# HEADERS_HAS_CCU.net
KiCad netlist of a schematic drawn in Altium Designer
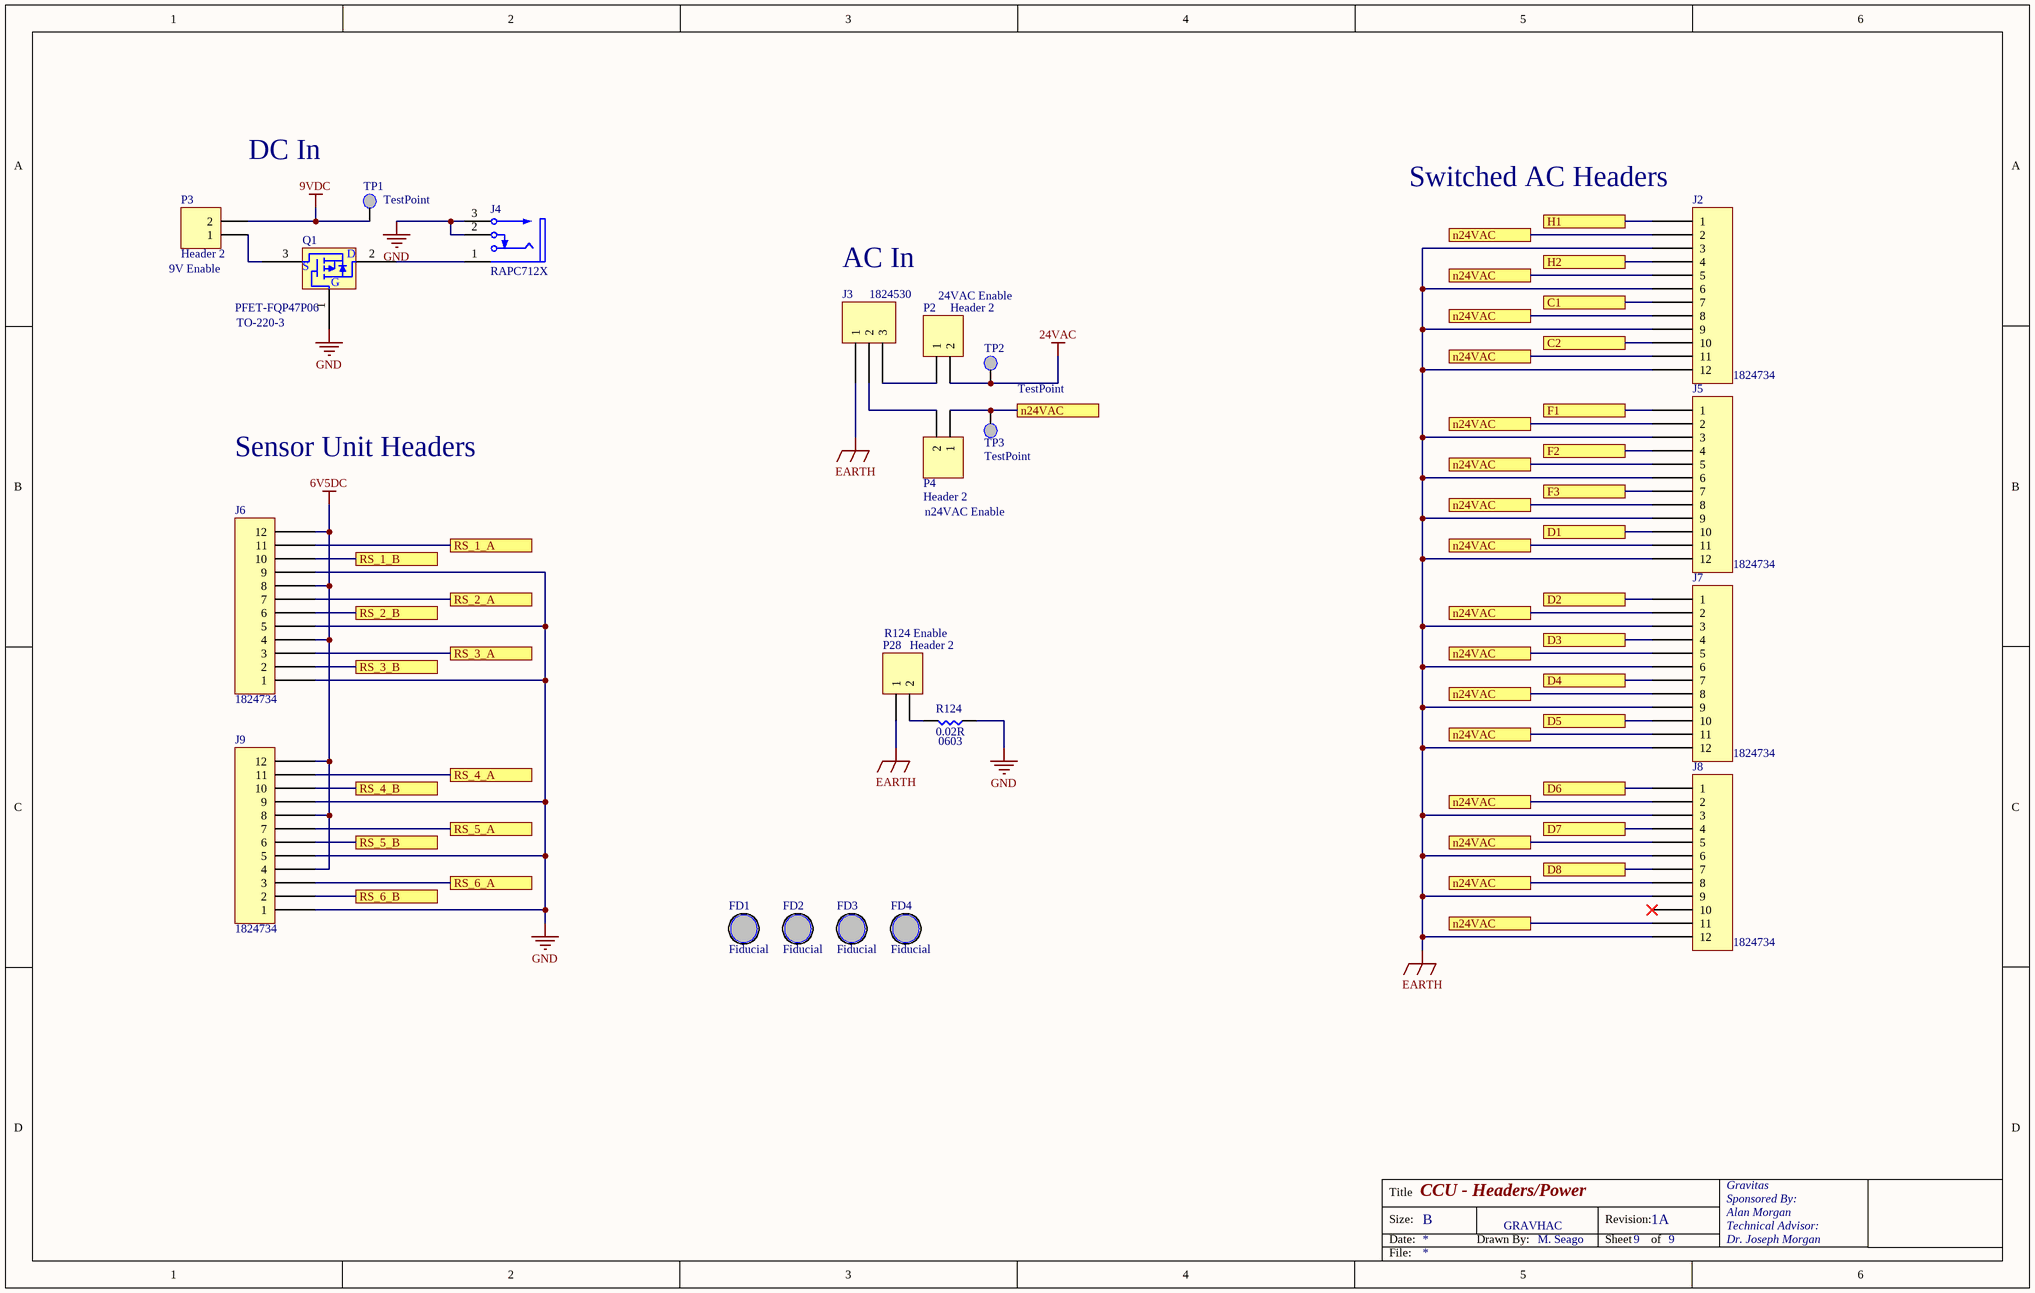
[diagram p0: HEADERS_HAS_CCU.SchDoc]

(export (version "E")
  (design (tool "Eeschema 10.0.6"))
  (components
    (comp (ref "FD1")
      (value "Fiducial")
      (footprint "Fiducial")
      (description "1mm pad, 2mm mask, 2mm KO")
      (libsource (lib "GravLib") (part "Fiducial"))
    )
    (comp (ref "FD2")
      (value "Fiducial")
      (footprint "Fiducial")
      (description "1mm pad, 2mm mask, 2mm KO")
      (libsource (lib "GravLib") (part "Fiducial"))
    )
    (comp (ref "FD3")
      (value "Fiducial")
      (footprint "Fiducial")
      (description "1mm pad, 2mm mask, 2mm KO")
      (libsource (lib "GravLib") (part "Fiducial"))
    )
    (comp (ref "FD4")
      (value "Fiducial")
      (footprint "Fiducial")
      (description "1mm pad, 2mm mask, 2mm KO")
      (libsource (lib "GravLib") (part "Fiducial"))
    )
    (comp (ref "J2") (value "1824734") (footprint "1824734") (libsource (lib "GravLib") (part "1824734")))
    (comp (ref "J3") (value "1824530") (footprint "1824530") (libsource (lib "GravLib") (part "1824530")))
    (comp (ref "J4")
      (value "RAPC712X")
      (footprint "SWITCH-RAPC712X-3_V")
      (description "Conn Powerjack Mini R/A PCMT, 5 A, 3-Pin THD, RoHS")
      (fields (field (name "MANUFACTURER") "Switchcraft"))
      (libsource (lib "Altium Content Vault") (part "SWITCH-RAPC712X-3"))
    )
    (comp (ref "J5") (value "1824734") (footprint "1824734") (libsource (lib "GravLib") (part "1824734")))
    (comp (ref "J6") (value "1824734") (footprint "1824734") (libsource (lib "") (part "1824734_1")))
    (comp (ref "J7") (value "1824734") (footprint "1824734") (libsource (lib "GravLib") (part "1824734")))
    (comp (ref "J8") (value "1824734") (footprint "1824734") (libsource (lib "GravLib") (part "1824734")))
    (comp (ref "J9") (value "1824734") (footprint "1824734") (libsource (lib "") (part "1824734_1")))
    (comp (ref "P2")
      (value "Header 2")
      (footprint "HDR1X2")
      (description "Header, 2-Pin")
      (fields (field (name "PUBLISHER") "Altium Limited"))
      (libsource (lib "") (part "Header 2_1"))
    )
    (comp (ref "P3")
      (value "Header 2")
      (footprint "HDR1X2")
      (description "Header, 2-Pin")
      (fields (field (name "PUBLISHER") "Altium Limited"))
      (libsource (lib "") (part "Header 2_2"))
    )
    (comp (ref "P4")
      (value "Header 2")
      (footprint "HDR1X2")
      (description "Header, 2-Pin")
      (fields (field (name "PUBLISHER") "Altium Limited"))
      (libsource (lib "Miscellaneous Connectors") (part "Header 2"))
    )
    (comp (ref "P28")
      (value "Header 2")
      (footprint "HDR1X2")
      (description "Header, 2-Pin")
      (fields (field (name "PUBLISHER") "Altium Limited"))
      (libsource (lib "") (part "Header 2_1"))
    )
    (comp (ref "Q1")
      (value "PFET-FQP47P06")
      (footprint "3-PIn?")
      (libsource (lib "GravLib") (part "PFET-FQP47P06"))
    )
    (comp (ref "R124")
      (value "0.02R")
      (footprint "NonPolar-0603")
      (libsource (lib "GravLib") (part "Res - 0603"))
    )
    (comp (ref "TP1")
      (value "TestPoint")
      (footprint "TP - S2751-46R")
      (description "S2751-46R")
      (libsource (lib "GravLib") (part "TestPoint"))
    )
    (comp (ref "TP2")
      (value "TestPoint")
      (footprint "TP - S2751-46R")
      (description "S2751-46R")
      (libsource (lib "GravLib") (part "TestPoint"))
    )
    (comp (ref "TP3")
      (value "TestPoint")
      (footprint "TP - S2751-46R")
      (description "S2751-46R")
      (libsource (lib "GravLib") (part "TestPoint"))
    )
  )
  (nets
    (net (code "1") (name "/C1") (class "Default")
      (node (ref "J2") (pin "7") (pinfunction "7_7") (pintype "passive"))
    )
    (net (code "2") (name "/C2") (class "Default")
      (node (ref "J2") (pin "10") (pinfunction "10_10") (pintype "passive"))
    )
    (net (code "3") (name "/D1") (class "Default")
      (node (ref "J5") (pin "10") (pinfunction "10_10") (pintype "passive"))
    )
    (net (code "4") (name "/D2") (class "Default")
      (node (ref "J7") (pin "1") (pinfunction "1_1") (pintype "passive"))
    )
    (net (code "5") (name "/D3") (class "Default")
      (node (ref "J7") (pin "4") (pinfunction "4_4") (pintype "passive"))
    )
    (net (code "6") (name "/D4") (class "Default")
      (node (ref "J7") (pin "7") (pinfunction "7_7") (pintype "passive"))
    )
    (net (code "7") (name "/D5") (class "Default")
      (node (ref "J7") (pin "10") (pinfunction "10_10") (pintype "passive"))
    )
    (net (code "8") (name "/D6") (class "Default")
      (node (ref "J8") (pin "1") (pinfunction "1_1") (pintype "passive"))
    )
    (net (code "9") (name "/D7") (class "Default")
      (node (ref "J8") (pin "4") (pinfunction "4_4") (pintype "passive"))
    )
    (net (code "10") (name "/D8") (class "Default")
      (node (ref "J8") (pin "7") (pinfunction "7_7") (pintype "passive"))
    )
    (net (code "11") (name "/F1") (class "Default")
      (node (ref "J5") (pin "1") (pinfunction "1_1") (pintype "passive"))
    )
    (net (code "12") (name "/F2") (class "Default")
      (node (ref "J5") (pin "4") (pinfunction "4_4") (pintype "passive"))
    )
    (net (code "13") (name "/F3") (class "Default")
      (node (ref "J5") (pin "7") (pinfunction "7_7") (pintype "passive"))
    )
    (net (code "14") (name "/H1") (class "Default")
      (node (ref "J2") (pin "1") (pinfunction "1_1") (pintype "passive"))
    )
    (net (code "15") (name "/H2") (class "Default")
      (node (ref "J2") (pin "4") (pinfunction "4_4") (pintype "passive"))
    )
    (net (code "16") (name "/RS_1_A") (class "Default")
      (node (ref "J6") (pin "11") (pinfunction "11_11") (pintype "passive"))
    )
    (net (code "17") (name "/RS_1_B") (class "Default")
      (node (ref "J6") (pin "10") (pinfunction "10_10") (pintype "passive"))
    )
    (net (code "18") (name "/RS_2_A") (class "Default")
      (node (ref "J6") (pin "7") (pinfunction "7_7") (pintype "passive"))
    )
    (net (code "19") (name "/RS_2_B") (class "Default")
      (node (ref "J6") (pin "6") (pinfunction "6_6") (pintype "passive"))
    )
    (net (code "20") (name "/RS_3_A") (class "Default")
      (node (ref "J6") (pin "3") (pinfunction "3_3") (pintype "passive"))
    )
    (net (code "21") (name "/RS_3_B") (class "Default")
      (node (ref "J6") (pin "2") (pinfunction "2_2") (pintype "passive"))
    )
    (net (code "22") (name "/RS_4_A") (class "Default")
      (node (ref "J9") (pin "11") (pinfunction "11_11") (pintype "passive"))
    )
    (net (code "23") (name "/RS_4_B") (class "Default")
      (node (ref "J9") (pin "10") (pinfunction "10_10") (pintype "passive"))
    )
    (net (code "24") (name "/RS_5_A") (class "Default")
      (node (ref "J9") (pin "7") (pinfunction "7_7") (pintype "passive"))
    )
    (net (code "25") (name "/RS_5_B") (class "Default")
      (node (ref "J9") (pin "6") (pinfunction "6_6") (pintype "passive"))
    )
    (net (code "26") (name "/RS_6_A") (class "Default")
      (node (ref "J9") (pin "3") (pinfunction "3_3") (pintype "passive"))
    )
    (net (code "27") (name "/RS_6_B") (class "Default")
      (node (ref "J9") (pin "2") (pinfunction "2_2") (pintype "passive"))
    )
    (net (code "28") (name "/n24VAC") (class "Default")
      (node (ref "J2") (pin "11") (pinfunction "11_11") (pintype "passive"))
      (node (ref "J2") (pin "2") (pinfunction "2_2") (pintype "passive"))
      (node (ref "J2") (pin "5") (pinfunction "5_5") (pintype "passive"))
      (node (ref "J2") (pin "8") (pinfunction "8_8") (pintype "passive"))
      (node (ref "J5") (pin "11") (pinfunction "11_11") (pintype "passive"))
      (node (ref "J5") (pin "2") (pinfunction "2_2") (pintype "passive"))
      (node (ref "J5") (pin "5") (pinfunction "5_5") (pintype "passive"))
      (node (ref "J5") (pin "8") (pinfunction "8_8") (pintype "passive"))
      (node (ref "J7") (pin "11") (pinfunction "11_11") (pintype "passive"))
      (node (ref "J7") (pin "2") (pinfunction "2_2") (pintype "passive"))
      (node (ref "J7") (pin "5") (pinfunction "5_5") (pintype "passive"))
      (node (ref "J7") (pin "8") (pinfunction "8_8") (pintype "passive"))
      (node (ref "J8") (pin "11") (pinfunction "11_11") (pintype "passive"))
      (node (ref "J8") (pin "2") (pinfunction "2_2") (pintype "passive"))
      (node (ref "J8") (pin "5") (pinfunction "5_5") (pintype "passive"))
      (node (ref "J8") (pin "8") (pinfunction "8_8") (pintype "passive"))
      (node (ref "P4") (pin "1") (pinfunction "1_1") (pintype "passive"))
      (node (ref "TP3") (pin "1") (pinfunction "1_1") (pintype "passive"))
    )
    (net (code "29") (name "6V5DC") (class "Default")
      (node (ref "J6") (pin "12") (pinfunction "12_12") (pintype "passive"))
      (node (ref "J6") (pin "4") (pinfunction "4_4") (pintype "passive"))
      (node (ref "J6") (pin "8") (pinfunction "8_8") (pintype "passive"))
      (node (ref "J9") (pin "12") (pinfunction "12_12") (pintype "passive"))
      (node (ref "J9") (pin "4") (pinfunction "4_4") (pintype "passive"))
      (node (ref "J9") (pin "8") (pinfunction "8_8") (pintype "passive"))
    )
    (net (code "30") (name "9VDC") (class "Default")
      (node (ref "P3") (pin "2") (pinfunction "2_2") (pintype "passive"))
      (node (ref "TP1") (pin "1") (pinfunction "1_1") (pintype "passive"))
    )
    (net (code "31") (name "24VAC") (class "Default")
      (node (ref "P2") (pin "2") (pinfunction "2_2") (pintype "passive"))
      (node (ref "TP2") (pin "1") (pinfunction "1_1") (pintype "passive"))
    )
    (net (code "32") (name "EARTH") (class "Default")
      (node (ref "J2") (pin "12") (pinfunction "12_12") (pintype "passive"))
      (node (ref "J2") (pin "3") (pinfunction "3_3") (pintype "passive"))
      (node (ref "J2") (pin "6") (pinfunction "6_6") (pintype "passive"))
      (node (ref "J2") (pin "9") (pinfunction "9_9") (pintype "passive"))
      (node (ref "J3") (pin "1") (pinfunction "1_1") (pintype "passive"))
      (node (ref "J5") (pin "12") (pinfunction "12_12") (pintype "passive"))
      (node (ref "J5") (pin "3") (pinfunction "3_3") (pintype "passive"))
      (node (ref "J5") (pin "6") (pinfunction "6_6") (pintype "passive"))
      (node (ref "J5") (pin "9") (pinfunction "9_9") (pintype "passive"))
      (node (ref "J7") (pin "12") (pinfunction "12_12") (pintype "passive"))
      (node (ref "J7") (pin "3") (pinfunction "3_3") (pintype "passive"))
      (node (ref "J7") (pin "6") (pinfunction "6_6") (pintype "passive"))
      (node (ref "J7") (pin "9") (pinfunction "9_9") (pintype "passive"))
      (node (ref "J8") (pin "12") (pinfunction "12_12") (pintype "passive"))
      (node (ref "J8") (pin "3") (pinfunction "3_3") (pintype "passive"))
      (node (ref "J8") (pin "6") (pinfunction "6_6") (pintype "passive"))
      (node (ref "J8") (pin "9") (pinfunction "9_9") (pintype "passive"))
      (node (ref "P28") (pin "1") (pinfunction "1_1") (pintype "passive"))
    )
    (net (code "33") (name "GND") (class "Default")
      (node (ref "J4") (pin "2") (pinfunction "2_2") (pintype "passive"))
      (node (ref "J4") (pin "3") (pinfunction "3_3") (pintype "passive"))
      (node (ref "J6") (pin "1") (pinfunction "1_1") (pintype "passive"))
      (node (ref "J6") (pin "5") (pinfunction "5_5") (pintype "passive"))
      (node (ref "J6") (pin "9") (pinfunction "9_9") (pintype "passive"))
      (node (ref "J9") (pin "1") (pinfunction "1_1") (pintype "passive"))
      (node (ref "J9") (pin "5") (pinfunction "5_5") (pintype "passive"))
      (node (ref "J9") (pin "9") (pinfunction "9_9") (pintype "passive"))
      (node (ref "Q1") (pin "1") (pinfunction "1_1") (pintype "passive"))
      (node (ref "R124") (pin "2") (pinfunction "2_2") (pintype "passive"))
    )
    (net (code "34") (name "Net-(J3-Pad2)") (class "Default")
      (node (ref "J3") (pin "2") (pinfunction "2_2") (pintype "passive"))
      (node (ref "P4") (pin "2") (pinfunction "2_2") (pintype "passive"))
    )
    (net (code "35") (name "Net-(J3-Pad3)") (class "Default")
      (node (ref "J3") (pin "3") (pinfunction "3_3") (pintype "passive"))
      (node (ref "P2") (pin "1") (pinfunction "1_1") (pintype "passive"))
    )
    (net (code "36") (name "Net-(J4-Pad1)") (class "Default")
      (node (ref "J4") (pin "1") (pinfunction "1_1") (pintype "passive"))
      (node (ref "Q1") (pin "2") (pinfunction "2_2") (pintype "passive"))
    )
    (net (code "37") (name "Net-(P3-Pad1)") (class "Default")
      (node (ref "P3") (pin "1") (pinfunction "1_1") (pintype "passive"))
      (node (ref "Q1") (pin "3") (pinfunction "3_3") (pintype "passive"))
    )
    (net (code "38") (name "Net-(P28-Pad2)") (class "Default")
      (node (ref "P28") (pin "2") (pinfunction "2_2") (pintype "passive"))
      (node (ref "R124") (pin "1") (pinfunction "1_1") (pintype "passive"))
    )
    (net (code "39") (name "unconnected-(J8-Pad10)") (class "Default")
      (node (ref "J8") (pin "10") (pinfunction "10_10") (pintype "passive+no_connect"))
    )
  )
)
